# hmi.net
KiCad netlist of a schematic drawn in Altium Designer
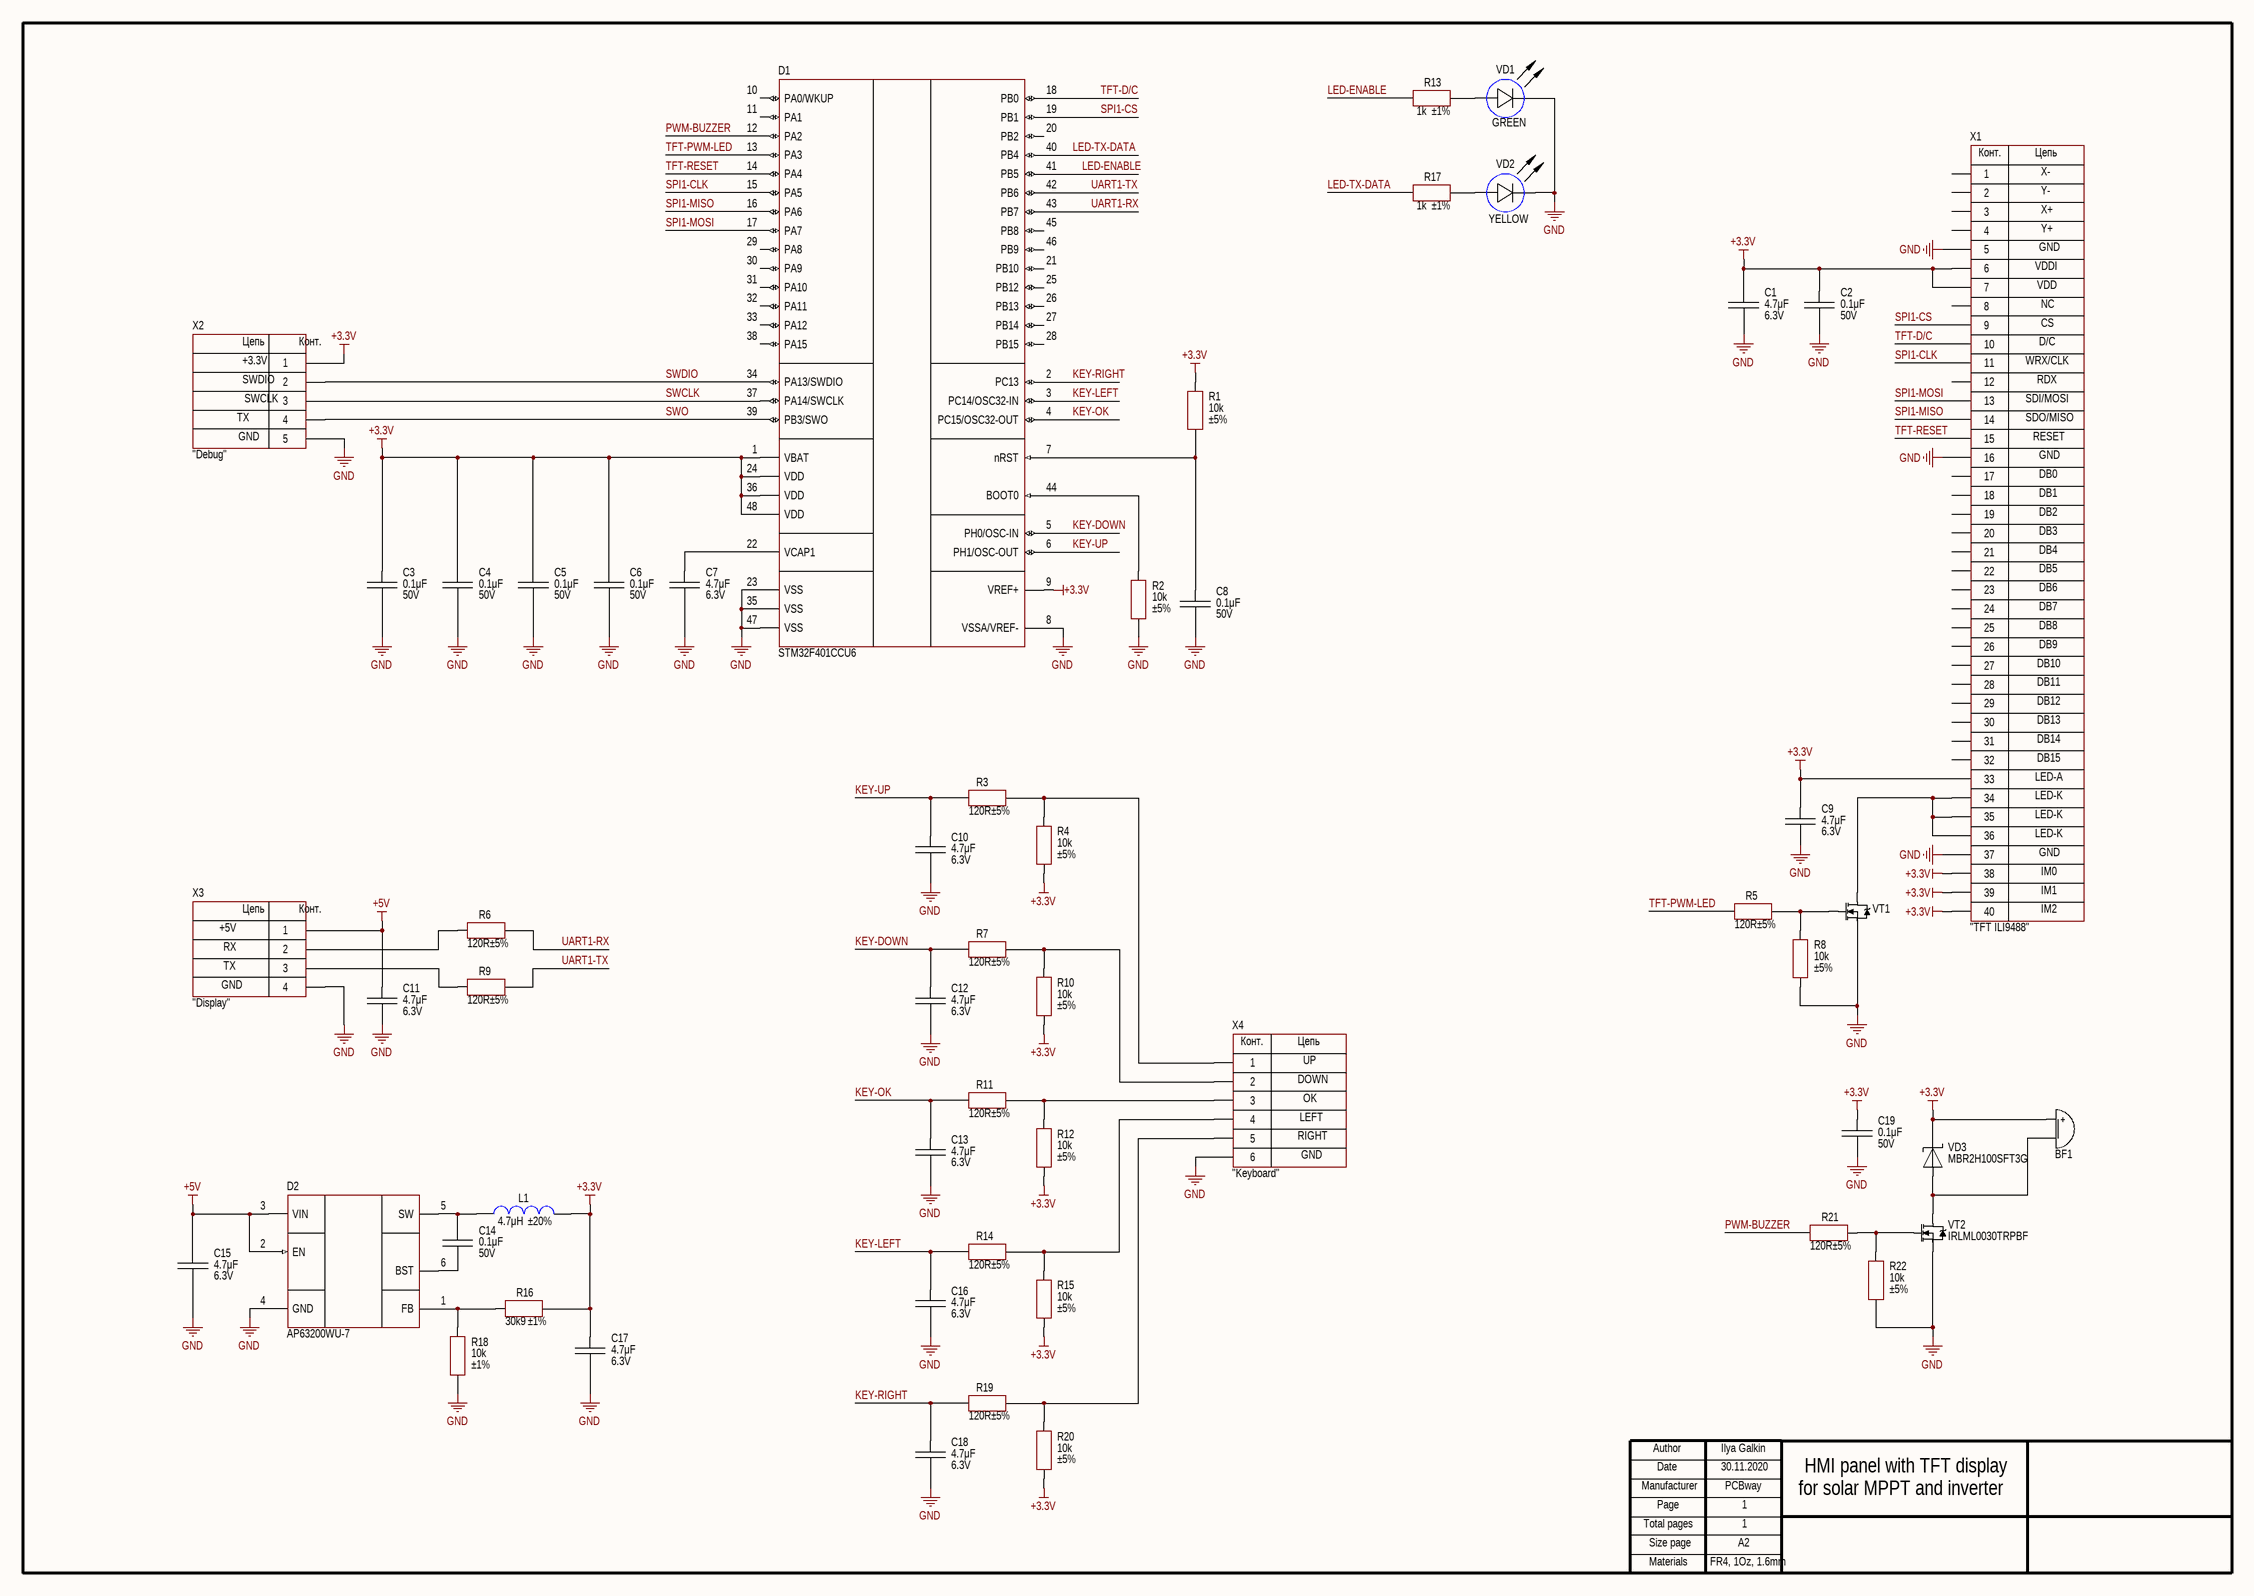
[diagram p0: hmi.SchDoc]

(export (version "E")
  (design (tool "Eeschema 10.0.6"))
  (components
    (comp (ref "BF1")
      (value "~")
      (footprint "BUZ: CMT-7525")
      (fields
        (field (name "MANUFACTURER") "Jiangsu")
        (field (name "VALUEMANUFACTURERPARTNUMBER") "SMD, 7.5x7.5x2.5 mm, 2.7 kHz, 3.6VDC, 80dB, -20...+70°C")
        (field (name "PARTNUMBER") "MLT-7525")
      )
      (libsource (lib "electromechanics") (part "Buzzer"))
    )
    (comp (ref "C1")
      (value "4.7μF")
      (footprint "CAP: 0603")
      (fields
        (field (name "MANUFACTURER") "Samsung")
        (field (name "PARTNUMBER") "CL10B475KQ8NQNC")
        (field (name "VALUEMANUFACTURERPARTNUMBER") "Ceramic capacitor, 4.7μF, X7R, ±10%, 6.3V, 0603, -55...+125°C")
        (field (name "VOLTAGE") "6.3V")
      )
      (libsource (lib "Capacitor") (part "Ceramic_0603"))
    )
    (comp (ref "C2")
      (value "0.1μF")
      (footprint "CAP: 0603")
      (fields
        (field (name "MANUFACTURER") "Samsung")
        (field (name "PARTNUMBER") "CL10B104KB8WPND")
        (field (name "VALUEMANUFACTURERPARTNUMBER") "Ceramic capacitor, 0.1μF, X7R, ±10%, 50V, 0603, -55...+125°C")
        (field (name "VOLTAGE") "50V")
      )
      (libsource (lib "Capacitor") (part "Ceramic_0603"))
    )
    (comp (ref "C3")
      (value "0.1μF")
      (footprint "CAP: 0603")
      (fields
        (field (name "MANUFACTURER") "Samsung")
        (field (name "PARTNUMBER") "CL10B104KB8WPND")
        (field (name "VALUEMANUFACTURERPARTNUMBER") "Ceramic capacitor, 0.1μF, X7R, ±10%, 50V, 0603, -55...+125°C")
        (field (name "VOLTAGE") "50V")
      )
      (libsource (lib "Capacitor") (part "Ceramic_0603"))
    )
    (comp (ref "C4")
      (value "0.1μF")
      (footprint "CAP: 0603")
      (fields
        (field (name "MANUFACTURER") "Samsung")
        (field (name "PARTNUMBER") "CL10B104KB8WPND")
        (field (name "VALUEMANUFACTURERPARTNUMBER") "Ceramic capacitor, 0.1μF, X7R, ±10%, 50V, 0603, -55...+125°C")
        (field (name "VOLTAGE") "50V")
      )
      (libsource (lib "Capacitor") (part "Ceramic_0603"))
    )
    (comp (ref "C5")
      (value "0.1μF")
      (footprint "CAP: 0603")
      (fields
        (field (name "MANUFACTURER") "Samsung")
        (field (name "PARTNUMBER") "CL10B104KB8WPND")
        (field (name "VALUEMANUFACTURERPARTNUMBER") "Ceramic capacitor, 0.1μF, X7R, ±10%, 50V, 0603, -55...+125°C")
        (field (name "VOLTAGE") "50V")
      )
      (libsource (lib "Capacitor") (part "Ceramic_0603"))
    )
    (comp (ref "C6")
      (value "0.1μF")
      (footprint "CAP: 0603")
      (fields
        (field (name "MANUFACTURER") "Samsung")
        (field (name "PARTNUMBER") "CL10B104KB8WPND")
        (field (name "VALUEMANUFACTURERPARTNUMBER") "Ceramic capacitor, 0.1μF, X7R, ±10%, 50V, 0603, -55...+125°C")
        (field (name "VOLTAGE") "50V")
      )
      (libsource (lib "Capacitor") (part "Ceramic_0603"))
    )
    (comp (ref "C7")
      (value "4.7μF")
      (footprint "CAP: 0603")
      (fields
        (field (name "MANUFACTURER") "Samsung")
        (field (name "PARTNUMBER") "CL10B475KQ8NQNC")
        (field (name "VALUEMANUFACTURERPARTNUMBER") "Ceramic capacitor, 4.7μF, X7R, ±10%, 6.3V, 0603, -55...+125°C")
        (field (name "VOLTAGE") "6.3V")
      )
      (libsource (lib "Capacitor") (part "Ceramic_0603"))
    )
    (comp (ref "C8")
      (value "0.1μF")
      (footprint "CAP: 0603")
      (fields
        (field (name "MANUFACTURER") "Samsung")
        (field (name "PARTNUMBER") "CL10B104KB8WPND")
        (field (name "VALUEMANUFACTURERPARTNUMBER") "Ceramic capacitor, 0.1μF, X7R, ±10%, 50V, 0603, -55...+125°C")
        (field (name "VOLTAGE") "50V")
      )
      (libsource (lib "Capacitor") (part "Ceramic_0603"))
    )
    (comp (ref "C9")
      (value "4.7μF")
      (footprint "CAP: 0603")
      (fields
        (field (name "MANUFACTURER") "Samsung")
        (field (name "PARTNUMBER") "CL10B475KQ8NQNC")
        (field (name "VALUEMANUFACTURERPARTNUMBER") "Ceramic capacitor, 4.7μF, X7R, ±10%, 6.3V, 0603, -55...+125°C")
        (field (name "VOLTAGE") "6.3V")
      )
      (libsource (lib "Capacitor") (part "Ceramic_0603"))
    )
    (comp (ref "C10")
      (value "4.7μF")
      (footprint "CAP: 0603")
      (fields
        (field (name "MANUFACTURER") "Samsung")
        (field (name "PARTNUMBER") "CL10B475KQ8NQNC")
        (field (name "VALUEMANUFACTURERPARTNUMBER") "Ceramic capacitor, 4.7μF, X7R, ±10%, 6.3V, 0603, -55...+125°C")
        (field (name "VOLTAGE") "6.3V")
      )
      (libsource (lib "Capacitor") (part "Ceramic_0603"))
    )
    (comp (ref "C11")
      (value "4.7μF")
      (footprint "CAP: 0603")
      (fields
        (field (name "MANUFACTURER") "Samsung")
        (field (name "PARTNUMBER") "CL10B475KQ8NQNC")
        (field (name "VALUEMANUFACTURERPARTNUMBER") "Ceramic capacitor, 4.7μF, X7R, ±10%, 6.3V, 0603, -55...+125°C")
        (field (name "VOLTAGE") "6.3V")
      )
      (libsource (lib "Capacitor") (part "Ceramic_0603"))
    )
    (comp (ref "C12")
      (value "4.7μF")
      (footprint "CAP: 0603")
      (fields
        (field (name "MANUFACTURER") "Samsung")
        (field (name "PARTNUMBER") "CL10B475KQ8NQNC")
        (field (name "VALUEMANUFACTURERPARTNUMBER") "Ceramic capacitor, 4.7μF, X7R, ±10%, 6.3V, 0603, -55...+125°C")
        (field (name "VOLTAGE") "6.3V")
      )
      (libsource (lib "Capacitor") (part "Ceramic_0603"))
    )
    (comp (ref "C13")
      (value "4.7μF")
      (footprint "CAP: 0603")
      (fields
        (field (name "MANUFACTURER") "Samsung")
        (field (name "PARTNUMBER") "CL10B475KQ8NQNC")
        (field (name "VALUEMANUFACTURERPARTNUMBER") "Ceramic capacitor, 4.7μF, X7R, ±10%, 6.3V, 0603, -55...+125°C")
        (field (name "VOLTAGE") "6.3V")
      )
      (libsource (lib "Capacitor") (part "Ceramic_0603"))
    )
    (comp (ref "C14")
      (value "0.1μF")
      (footprint "CAP: 0603")
      (fields
        (field (name "MANUFACTURER") "Samsung")
        (field (name "PARTNUMBER") "CL10B104KB8WPND")
        (field (name "VALUEMANUFACTURERPARTNUMBER") "Ceramic capacitor, 0.1μF, X7R, ±10%, 50V, 0603, -55...+125°C")
        (field (name "VOLTAGE") "50V")
      )
      (libsource (lib "Capacitor") (part "Ceramic_0603"))
    )
    (comp (ref "C15")
      (value "4.7μF")
      (footprint "CAP: 0603")
      (fields
        (field (name "MANUFACTURER") "Samsung")
        (field (name "PARTNUMBER") "CL10B475KQ8NQNC")
        (field (name "VALUEMANUFACTURERPARTNUMBER") "Ceramic capacitor, 4.7μF, X7R, ±10%, 6.3V, 0603, -55...+125°C")
        (field (name "VOLTAGE") "6.3V")
      )
      (libsource (lib "Capacitor") (part "Ceramic_0603"))
    )
    (comp (ref "C16")
      (value "4.7μF")
      (footprint "CAP: 0603")
      (fields
        (field (name "MANUFACTURER") "Samsung")
        (field (name "PARTNUMBER") "CL10B475KQ8NQNC")
        (field (name "VALUEMANUFACTURERPARTNUMBER") "Ceramic capacitor, 4.7μF, X7R, ±10%, 6.3V, 0603, -55...+125°C")
        (field (name "VOLTAGE") "6.3V")
      )
      (libsource (lib "Capacitor") (part "Ceramic_0603"))
    )
    (comp (ref "C17")
      (value "4.7μF")
      (footprint "CAP: 0603")
      (fields
        (field (name "MANUFACTURER") "Samsung")
        (field (name "PARTNUMBER") "CL10B475KQ8NQNC")
        (field (name "VALUEMANUFACTURERPARTNUMBER") "Ceramic capacitor, 4.7μF, X7R, ±10%, 6.3V, 0603, -55...+125°C")
        (field (name "VOLTAGE") "6.3V")
      )
      (libsource (lib "Capacitor") (part "Ceramic_0603"))
    )
    (comp (ref "C18")
      (value "4.7μF")
      (footprint "CAP: 0603")
      (fields
        (field (name "MANUFACTURER") "Samsung")
        (field (name "PARTNUMBER") "CL10B475KQ8NQNC")
        (field (name "VALUEMANUFACTURERPARTNUMBER") "Ceramic capacitor, 4.7μF, X7R, ±10%, 6.3V, 0603, -55...+125°C")
        (field (name "VOLTAGE") "6.3V")
      )
      (libsource (lib "Capacitor") (part "Ceramic_0603"))
    )
    (comp (ref "C19")
      (value "0.1μF")
      (footprint "CAP: 0603")
      (fields
        (field (name "MANUFACTURER") "Samsung")
        (field (name "PARTNUMBER") "CL10B104KB8WPND")
        (field (name "VALUEMANUFACTURERPARTNUMBER") "Ceramic capacitor, 0.1μF, X7R, ±10%, 50V, 0603, -55...+125°C")
        (field (name "VOLTAGE") "50V")
      )
      (libsource (lib "Capacitor") (part "Ceramic_0603"))
    )
    (comp (ref "D1")
      (value "~")
      (footprint "48-QFN (7x7)")
      (description "Cortex-M4")
      (fields (field (name "MANUFACTURER") "STMicroelectronics") (field (name "PARTNUMBER") "STM32F401CCU6"))
      (libsource (lib "ic-mcu") (part "STM32F401CCU6"))
    )
    (comp (ref "D2")
      (value "~")
      (footprint "SOT23-6")
      (description "Buck converter")
      (fields
        (field (name "MANUFACTURER") "Diodes")
        (field (name "VALUEMANUFACTURERPARTNUMBER") "DC/DC buck converter, input 3.8...32V, 500kHz, output 1.2...12V, 2A, -40...+85°C, SOT23-6")
        (field (name "PARTNUMBER") "AP63200WU-7")
      )
      (libsource (lib "ic-power-supply") (part "AP63200WU-7"))
    )
    (comp (ref "L1")
      (value "4.7μH")
      (footprint "IND: CD32")
      (fields
        (field (name "MANUFACTURER") "YJYCOIN")
        (field (name "PARTNUMBER") "CD32YP0302-4R7M")
        (field (name "VALUEMANUFACTURERPARTNUMBER") "Fixed inductor, 4.7μH, ±20%, CD32 series, 1.5A, -40...+125°C")
        (field (name "TOLERANCE") "±20%")
      )
      (libsource (lib "inductor") (part "Inductor_CD32"))
    )
    (comp (ref "R1")
      (value "10k")
      (footprint "RES: 0603")
      (fields
        (field (name "MANUFACTURER") "Yageo")
        (field (name "PARTNUMBER") "RC0603JR-0710KL")
        (field (name "VALUEMANUFACTURERPARTNUMBER") "Resistor film, 10k, ±5%, 0603, 0.1W, -55...+125°C")
        (field (name "TOLERANCE") "±5%")
      )
      (libsource (lib "Resistor") (part "Resistor_0603"))
    )
    (comp (ref "R2")
      (value "10k")
      (footprint "RES: 0603")
      (fields
        (field (name "MANUFACTURER") "Yageo")
        (field (name "PARTNUMBER") "RC0603JR-0710KL")
        (field (name "VALUEMANUFACTURERPARTNUMBER") "Resistor film, 10k, ±5%, 0603, 0.1W, -55...+125°C")
        (field (name "TOLERANCE") "±5%")
      )
      (libsource (lib "Resistor") (part "Resistor_0603"))
    )
    (comp (ref "R3")
      (value "120R")
      (footprint "RES: 0603")
      (fields
        (field (name "MANUFACTURER") "Yageo")
        (field (name "PARTNUMBER") "RC0603JR-07120RL")
        (field (name "VALUEMANUFACTURERPARTNUMBER") "Resistor film, 120R, ±5%, 0603, 0.1W, -55...+125°C")
        (field (name "TOLERANCE") "±5%")
      )
      (libsource (lib "resistor") (part "Resistor_0603"))
    )
    (comp (ref "R4")
      (value "10k")
      (footprint "RES: 0603")
      (fields
        (field (name "MANUFACTURER") "Yageo")
        (field (name "PARTNUMBER") "RC0603JR-0710KL")
        (field (name "VALUEMANUFACTURERPARTNUMBER") "Resistor film, 10k, ±5%, 0603, 0.1W, -55...+125°C")
        (field (name "TOLERANCE") "±5%")
      )
      (libsource (lib "Resistor") (part "Resistor_0603"))
    )
    (comp (ref "R5")
      (value "120R")
      (footprint "RES: 0603")
      (fields
        (field (name "MANUFACTURER") "Yageo")
        (field (name "PARTNUMBER") "RC0603JR-07120RL")
        (field (name "VALUEMANUFACTURERPARTNUMBER") "Resistor film, 120R, ±5%, 0603, 0.1W, -55...+125°C")
        (field (name "TOLERANCE") "±5%")
      )
      (libsource (lib "") (part "Resistor_0603_1"))
    )
    (comp (ref "R6")
      (value "120R")
      (footprint "RES: 0603")
      (fields
        (field (name "MANUFACTURER") "Yageo")
        (field (name "PARTNUMBER") "RC0603JR-07120RL")
        (field (name "VALUEMANUFACTURERPARTNUMBER") "Resistor film, 120R, ±5%, 0603, 0.1W, -55...+125°C")
        (field (name "TOLERANCE") "±5%")
      )
      (libsource (lib "") (part "Resistor_0603_1"))
    )
    (comp (ref "R7")
      (value "120R")
      (footprint "RES: 0603")
      (fields
        (field (name "MANUFACTURER") "Yageo")
        (field (name "PARTNUMBER") "RC0603JR-07120RL")
        (field (name "VALUEMANUFACTURERPARTNUMBER") "Resistor film, 120R, ±5%, 0603, 0.1W, -55...+125°C")
        (field (name "TOLERANCE") "±5%")
      )
      (libsource (lib "resistor") (part "Resistor_0603"))
    )
    (comp (ref "R8")
      (value "10k")
      (footprint "RES: 0603")
      (fields
        (field (name "MANUFACTURER") "Yageo")
        (field (name "PARTNUMBER") "RC0603JR-0710KL")
        (field (name "VALUEMANUFACTURERPARTNUMBER") "Resistor film, 10k, ±5%, 0603, 0.1W, -55...+125°C")
        (field (name "TOLERANCE") "±5%")
      )
      (libsource (lib "Resistor") (part "Resistor_0603"))
    )
    (comp (ref "R9")
      (value "120R")
      (footprint "RES: 0603")
      (fields
        (field (name "MANUFACTURER") "Yageo")
        (field (name "PARTNUMBER") "RC0603JR-07120RL")
        (field (name "VALUEMANUFACTURERPARTNUMBER") "Resistor film, 120R, ±5%, 0603, 0.1W, -55...+125°C")
        (field (name "TOLERANCE") "±5%")
      )
      (libsource (lib "") (part "Resistor_0603_1"))
    )
    (comp (ref "R10")
      (value "10k")
      (footprint "RES: 0603")
      (fields
        (field (name "MANUFACTURER") "Yageo")
        (field (name "PARTNUMBER") "RC0603JR-0710KL")
        (field (name "VALUEMANUFACTURERPARTNUMBER") "Resistor film, 10k, ±5%, 0603, 0.1W, -55...+125°C")
        (field (name "TOLERANCE") "±5%")
      )
      (libsource (lib "Resistor") (part "Resistor_0603"))
    )
    (comp (ref "R11")
      (value "120R")
      (footprint "RES: 0603")
      (fields
        (field (name "MANUFACTURER") "Yageo")
        (field (name "PARTNUMBER") "RC0603JR-07120RL")
        (field (name "VALUEMANUFACTURERPARTNUMBER") "Resistor film, 120R, ±5%, 0603, 0.1W, -55...+125°C")
        (field (name "TOLERANCE") "±5%")
      )
      (libsource (lib "resistor") (part "Resistor_0603"))
    )
    (comp (ref "R12")
      (value "10k")
      (footprint "RES: 0603")
      (fields
        (field (name "MANUFACTURER") "Yageo")
        (field (name "PARTNUMBER") "RC0603JR-0710KL")
        (field (name "VALUEMANUFACTURERPARTNUMBER") "Resistor film, 10k, ±5%, 0603, 0.1W, -55...+125°C")
        (field (name "TOLERANCE") "±5%")
      )
      (libsource (lib "Resistor") (part "Resistor_0603"))
    )
    (comp (ref "R13")
      (value "1k")
      (footprint "RES: 0603")
      (fields
        (field (name "MANUFACTURER") "Yageo")
        (field (name "PARTNUMBER") "RC0603JR-071KL")
        (field (name "VALUEMANUFACTURERPARTNUMBER") "Resistor film, 1k, ±1%, 0603, 0.1W, -55...+125°C")
        (field (name "TOLERANCE") "±1%")
      )
      (libsource (lib "") (part "Resistor_0603_2"))
    )
    (comp (ref "R14")
      (value "120R")
      (footprint "RES: 0603")
      (fields
        (field (name "MANUFACTURER") "Yageo")
        (field (name "PARTNUMBER") "RC0603JR-07120RL")
        (field (name "VALUEMANUFACTURERPARTNUMBER") "Resistor film, 120R, ±5%, 0603, 0.1W, -55...+125°C")
        (field (name "TOLERANCE") "±5%")
      )
      (libsource (lib "resistor") (part "Resistor_0603"))
    )
    (comp (ref "R15")
      (value "10k")
      (footprint "RES: 0603")
      (fields
        (field (name "MANUFACTURER") "Yageo")
        (field (name "PARTNUMBER") "RC0603JR-0710KL")
        (field (name "VALUEMANUFACTURERPARTNUMBER") "Resistor film, 10k, ±5%, 0603, 0.1W, -55...+125°C")
        (field (name "TOLERANCE") "±5%")
      )
      (libsource (lib "Resistor") (part "Resistor_0603"))
    )
    (comp (ref "R16")
      (value "30k9")
      (footprint "RES: 0603")
      (fields
        (field (name "MANUFACTURER") "Yageo")
        (field (name "PARTNUMBER") "RC0603FR-0730K9L")
        (field (name "VALUEMANUFACTURERPARTNUMBER") "Resistor film, 30k9, ±1%, 0603, 0.1W, -55...+125°C")
        (field (name "TOLERANCE") "±1%")
      )
      (libsource (lib "") (part "Resistor_0603_2"))
    )
    (comp (ref "R17")
      (value "1k")
      (footprint "RES: 0603")
      (fields
        (field (name "MANUFACTURER") "Yageo")
        (field (name "PARTNUMBER") "RC0603JR-071KL")
        (field (name "VALUEMANUFACTURERPARTNUMBER") "Resistor film, 1k, ±1%, 0603, 0.1W, -55...+125°C")
        (field (name "TOLERANCE") "±1%")
      )
      (libsource (lib "") (part "Resistor_0603_2"))
    )
    (comp (ref "R18")
      (value "10k")
      (footprint "RES: 0603")
      (fields
        (field (name "MANUFACTURER") "Yageo")
        (field (name "PARTNUMBER") "AC0603FR-0710KL")
        (field (name "VALUEMANUFACTURERPARTNUMBER") "Resistor film, 10k, ±1%, 0603, 0.1W, -55...+125°C")
        (field (name "TOLERANCE") "±1%")
      )
      (libsource (lib "Resistor") (part "Resistor_0603"))
    )
    (comp (ref "R19")
      (value "120R")
      (footprint "RES: 0603")
      (fields
        (field (name "MANUFACTURER") "Yageo")
        (field (name "PARTNUMBER") "RC0603JR-07120RL")
        (field (name "VALUEMANUFACTURERPARTNUMBER") "Resistor film, 120R, ±5%, 0603, 0.1W, -55...+125°C")
        (field (name "TOLERANCE") "±5%")
      )
      (libsource (lib "resistor") (part "Resistor_0603"))
    )
    (comp (ref "R20")
      (value "10k")
      (footprint "RES: 0603")
      (fields
        (field (name "MANUFACTURER") "Yageo")
        (field (name "PARTNUMBER") "RC0603JR-0710KL")
        (field (name "VALUEMANUFACTURERPARTNUMBER") "Resistor film, 10k, ±5%, 0603, 0.1W, -55...+125°C")
        (field (name "TOLERANCE") "±5%")
      )
      (libsource (lib "Resistor") (part "Resistor_0603"))
    )
    (comp (ref "R21")
      (value "120R")
      (footprint "RES: 0603")
      (fields
        (field (name "MANUFACTURER") "Yageo")
        (field (name "PARTNUMBER") "RC0603JR-07120RL")
        (field (name "VALUEMANUFACTURERPARTNUMBER") "Resistor film, 120R, ±5%, 0603, 0.1W, -55...+125°C")
        (field (name "TOLERANCE") "±5%")
      )
      (libsource (lib "") (part "Resistor_0603_1"))
    )
    (comp (ref "R22")
      (value "10k")
      (footprint "RES: 0603")
      (fields
        (field (name "MANUFACTURER") "Yageo")
        (field (name "PARTNUMBER") "RC0603JR-0710KL")
        (field (name "VALUEMANUFACTURERPARTNUMBER") "Resistor film, 10k, ±5%, 0603, 0.1W, -55...+125°C")
        (field (name "TOLERANCE") "±5%")
      )
      (libsource (lib "Resistor") (part "Resistor_0603"))
    )
    (comp (ref "VD1")
      (value "~")
      (footprint "LED: 0603G")
      (fields
        (field (name "MANUFACTURER") "Wurth")
        (field (name "VALUEMANUFACTURERPARTNUMBER") "LED, 20mA, 2V, 0603, -55...+150°C")
        (field (name "PARTNUMBER") "150060VS75000")
        (field (name "COLOR") "GREEN")
      )
      (libsource (lib "Diode") (part "LED_single"))
    )
    (comp (ref "VD2")
      (value "~")
      (footprint "LED: 0603Y")
      (fields
        (field (name "MANUFACTURER") "Wurth")
        (field (name "VALUEMANUFACTURERPARTNUMBER") "LED, 20mA, 2V, 0603, -55...+150°C")
        (field (name "PARTNUMBER") "150060YS75000")
        (field (name "COLOR") "YELLOW")
      )
      (libsource (lib "Diode") (part "LED_single"))
    )
    (comp (ref "VD3")
      (value "~")
      (footprint "DIODE: SOD123F")
      (fields
        (field (name "MANUFACTURER") "ON Semiconductor")
        (field (name "VALUEMANUFACTURERPARTNUMBER") "Schottky diode, 100V, 2A, 840mV, 15pF, SOD-123F, -55...+150°C")
        (field (name "VOLTAGE") "100V")
        (field (name "PARTNUMBER") "MBR2H100SFT3G")
      )
      (libsource (lib "Diode") (part "Schottky_single"))
    )
    (comp (ref "VT1")
      (value "~")
      (footprint "SOT23")
      (fields
        (field (name "MANUFACTURER") "Infineon Technologies")
        (field (name "VALUEMANUFACTURERPARTNUMBER") "MOSFET N-channel transistor, 30V, 5.3A, 2.6nC, 1.3W, 27mOhm, 382pF, SOT-23, -55...+150°C")
        (field (name "PARTNUMBER") "IRLML0030TRPBF")
      )
      (libsource (lib "transistor") (part "MOSFET_N_132"))
    )
    (comp (ref "VT2")
      (value "~")
      (footprint "SOT23")
      (fields
        (field (name "MANUFACTURER") "Infineon Technologies")
        (field (name "VALUEMANUFACTURERPARTNUMBER") "MOSFET N-channel transistor, 30V, 5.3A, 2.6nC, 1.3W, 27mOhm, 382pF, SOT-23, -55...+150°C")
        (field (name "PARTNUMBER") "IRLML0030TRPBF")
      )
      (libsource (lib "transistor") (part "MOSFET_N_132"))
    )
    (comp (ref "X1")
      (value "~")
      (footprint "CON: FFC/FPC-40-0.5")
      (fields
        (field (name "MANUFACTURER") "JUSHUO")
        (field (name "VALUEMANUFACTURERPARTNUMBER") "Connector, 40pin, 0.5mm, FFC/FPC, Top contact")
        (field (name "PARTNUMBER") "AFC07-S40ECC-00")
        (field (name "COMMENTTEXT") "\"TFT ILI9488\"")
      )
      (libsource (lib "connector") (part "Connector_FFC_40"))
    )
    (comp (ref "X2")
      (value "~")
      (footprint "CON: PLS-5")
      (fields
        (field (name "MANUFACTURER") "Connfly")
        (field (name "VALUEMANUFACTURERPARTNUMBER") "Connector, 5pin, 2.54mm, 500VAC, 3A")
        (field (name "PARTNUMBER") "PLS-5")
        (field (name "COMMENTTEXT") "\"Debug\"")
      )
      (libsource (lib "connector") (part "PLS-5"))
    )
    (comp (ref "X3")
      (value "~")
      (footprint "CON: CWF-4R")
      (fields
        (field (name "MANUFACTURER") "Connfly")
        (field (name "VALUEMANUFACTURERPARTNUMBER") "Connector, 4pin, 2.54mm, 250VAC, 3A")
        (field (name "PARTNUMBER") "CWF-4R")
        (field (name "COMMENTTEXT") "\"Display\"")
      )
      (libsource (lib "connector") (part "CWF-4"))
    )
    (comp (ref "X4")
      (value "~")
      (footprint "CON: CWF-6R")
      (fields
        (field (name "MANUFACTURER") "Connfly")
        (field (name "VALUEMANUFACTURERPARTNUMBER") "Connector, 6pin, 2.54mm, 250VAC, 3A")
        (field (name "PARTNUMBER") "CWF-6R")
        (field (name "COMMENTTEXT") "\"Keyboard\"")
      )
      (libsource (lib "connector") (part "CWF-6"))
    )
  )
  (nets
    (net (code "1") (name "+3.3V") (class "Default")
      (node (ref "BF1") (pin "1") (pinfunction "+_1") (pintype "passive"))
      (node (ref "C1") (pin "2") (pinfunction "2_2") (pintype "power_in"))
      (node (ref "C17") (pin "2") (pinfunction "2_2") (pintype "power_in"))
      (node (ref "C19") (pin "2") (pinfunction "2_2") (pintype "power_in"))
      (node (ref "C2") (pin "2") (pinfunction "2_2") (pintype "power_in"))
      (node (ref "C3") (pin "2") (pinfunction "2_2") (pintype "power_in"))
      (node (ref "C4") (pin "2") (pinfunction "2_2") (pintype "power_in"))
      (node (ref "C5") (pin "2") (pinfunction "2_2") (pintype "power_in"))
      (node (ref "C6") (pin "2") (pinfunction "2_2") (pintype "power_in"))
      (node (ref "C9") (pin "2") (pinfunction "2_2") (pintype "power_in"))
      (node (ref "D1") (pin "1") (pinfunction "VBAT_1") (pintype "passive"))
      (node (ref "D1") (pin "24") (pinfunction "VDD_24") (pintype "passive"))
      (node (ref "D1") (pin "36") (pinfunction "VDD_36") (pintype "passive"))
      (node (ref "D1") (pin "48") (pinfunction "VDD_48") (pintype "passive"))
      (node (ref "D1") (pin "9") (pinfunction "VREF+_9") (pintype "passive"))
      (node (ref "L1") (pin "1") (pinfunction "1_1") (pintype "passive"))
      (node (ref "R1") (pin "2") (pinfunction "2_2") (pintype "passive"))
      (node (ref "R10") (pin "1") (pinfunction "1_1") (pintype "passive"))
      (node (ref "R12") (pin "1") (pinfunction "1_1") (pintype "passive"))
      (node (ref "R15") (pin "1") (pinfunction "1_1") (pintype "passive"))
      (node (ref "R16") (pin "1") (pinfunction "1_1") (pintype "passive"))
      (node (ref "R20") (pin "1") (pinfunction "1_1") (pintype "passive"))
      (node (ref "R4") (pin "1") (pinfunction "1_1") (pintype "passive"))
      (node (ref "VD3") (pin "2") (pinfunction "2_2") (pintype "passive"))
      (node (ref "X1") (pin "33") (pinfunction "33_33") (pintype "passive"))
      (node (ref "X1") (pin "38") (pinfunction "38_38") (pintype "passive"))
      (node (ref "X1") (pin "39") (pinfunction "39_39") (pintype "passive"))
      (node (ref "X1") (pin "40") (pinfunction "40_40") (pintype "passive"))
      (node (ref "X1") (pin "6") (pinfunction "6_6") (pintype "passive"))
      (node (ref "X1") (pin "7") (pinfunction "7_7") (pintype "passive"))
      (node (ref "X2") (pin "1") (pinfunction "1_1") (pintype "passive"))
    )
    (net (code "2") (name "+5V") (class "Default")
      (node (ref "C11") (pin "2") (pinfunction "2_2") (pintype "power_in"))
      (node (ref "C15") (pin "2") (pinfunction "2_2") (pintype "power_in"))
      (node (ref "D2") (pin "2") (pinfunction "EN_2") (pintype "input"))
      (node (ref "D2") (pin "3") (pinfunction "VIN_3") (pintype "passive"))
      (node (ref "X3") (pin "1") (pinfunction "1_1") (pintype "passive"))
    )
    (net (code "3") (name "/KEY-DOWN") (class "Default")
      (node (ref "C12") (pin "2") (pinfunction "2_2") (pintype "power_in"))
      (node (ref "D1") (pin "5") (pinfunction "PH0/OSC-IN_5") (pintype "bidirectional"))
      (node (ref "R7") (pin "1") (pinfunction "1_1") (pintype "passive"))
    )
    (net (code "4") (name "/KEY-LEFT") (class "Default")
      (node (ref "C16") (pin "2") (pinfunction "2_2") (pintype "power_in"))
      (node (ref "D1") (pin "3") (pinfunction "PC14/OSC32-IN_3") (pintype "bidirectional"))
      (node (ref "R14") (pin "1") (pinfunction "1_1") (pintype "passive"))
    )
    (net (code "5") (name "/KEY-OK") (class "Default")
      (node (ref "C13") (pin "2") (pinfunction "2_2") (pintype "power_in"))
      (node (ref "D1") (pin "4") (pinfunction "PC15/OSC32-OUT_4") (pintype "bidirectional"))
      (node (ref "R11") (pin "1") (pinfunction "1_1") (pintype "passive"))
    )
    (net (code "6") (name "/KEY-RIGHT") (class "Default")
      (node (ref "C18") (pin "2") (pinfunction "2_2") (pintype "power_in"))
      (node (ref "D1") (pin "2") (pinfunction "PC13_2") (pintype "bidirectional"))
      (node (ref "R19") (pin "1") (pinfunction "1_1") (pintype "passive"))
    )
    (net (code "7") (name "/KEY-UP") (class "Default")
      (node (ref "C10") (pin "2") (pinfunction "2_2") (pintype "power_in"))
      (node (ref "D1") (pin "6") (pinfunction "PH1/OSC-OUT_6") (pintype "bidirectional"))
      (node (ref "R3") (pin "1") (pinfunction "1_1") (pintype "passive"))
    )
    (net (code "8") (name "/LED-ENABLE") (class "Default")
      (node (ref "D1") (pin "41") (pinfunction "PB5_41") (pintype "bidirectional"))
      (node (ref "R13") (pin "2") (pinfunction "2_2") (pintype "passive"))
    )
    (net (code "9") (name "/LED-TX-DATA") (class "Default")
      (node (ref "D1") (pin "40") (pinfunction "PB4_40") (pintype "bidirectional"))
      (node (ref "R17") (pin "2") (pinfunction "2_2") (pintype "passive"))
    )
    (net (code "10") (name "/PWM-BUZZER") (class "Default")
      (node (ref "D1") (pin "12") (pinfunction "PA2_12") (pintype "bidirectional"))
      (node (ref "R21") (pin "1") (pinfunction "1_1") (pintype "passive"))
    )
    (net (code "11") (name "/SPI1-CLK") (class "Default")
      (node (ref "D1") (pin "15") (pinfunction "PA5_15") (pintype "bidirectional"))
      (node (ref "X1") (pin "11") (pinfunction "11_11") (pintype "passive"))
    )
    (net (code "12") (name "/SPI1-CS") (class "Default")
      (node (ref "D1") (pin "19") (pinfunction "PB1_19") (pintype "bidirectional"))
      (node (ref "X1") (pin "9") (pinfunction "9_9") (pintype "passive"))
    )
    (net (code "13") (name "/SPI1-MISO") (class "Default")
      (node (ref "D1") (pin "16") (pinfunction "PA6_16") (pintype "bidirectional"))
      (node (ref "X1") (pin "14") (pinfunction "14_14") (pintype "passive"))
    )
    (net (code "14") (name "/SPI1-MOSI") (class "Default")
      (node (ref "D1") (pin "17") (pinfunction "PA7_17") (pintype "bidirectional"))
      (node (ref "X1") (pin "13") (pinfunction "13_13") (pintype "passive"))
    )
    (net (code "15") (name "/SWCLK") (class "Default")
      (node (ref "D1") (pin "37") (pinfunction "PA14/SWCLK_37") (pintype "bidirectional"))
      (node (ref "X2") (pin "3") (pinfunction "3_3") (pintype "power_in"))
    )
    (net (code "16") (name "/SWDIO") (class "Default")
      (node (ref "D1") (pin "34") (pinfunction "PA13/SWDIO_34") (pintype "bidirectional"))
      (node (ref "X2") (pin "2") (pinfunction "2_2") (pintype "passive"))
    )
    (net (code "17") (name "/SWO") (class "Default")
      (node (ref "D1") (pin "39") (pinfunction "PB3/SWO_39") (pintype "bidirectional"))
      (node (ref "X2") (pin "4") (pinfunction "4_4") (pintype "power_in"))
    )
    (net (code "18") (name "/TFT-D{slash}C") (class "Default")
      (node (ref "D1") (pin "18") (pinfunction "PB0_18") (pintype "bidirectional"))
      (node (ref "X1") (pin "10") (pinfunction "10_10") (pintype "passive"))
    )
    (net (code "19") (name "/TFT-PWM-LED") (class "Default")
      (node (ref "D1") (pin "13") (pinfunction "PA3_13") (pintype "bidirectional"))
      (node (ref "R5") (pin "1") (pinfunction "1_1") (pintype "passive"))
    )
    (net (code "20") (name "/TFT-RESET") (class "Default")
      (node (ref "D1") (pin "14") (pinfunction "PA4_14") (pintype "bidirectional"))
      (node (ref "X1") (pin "15") (pinfunction "15_15") (pintype "passive"))
    )
    (net (code "21") (name "/UART1-RX") (class "Default")
      (node (ref "D1") (pin "43") (pinfunction "PB7_43") (pintype "bidirectional"))
      (node (ref "R6") (pin "2") (pinfunction "2_2") (pintype "passive"))
    )
    (net (code "22") (name "/UART1-TX") (class "Default")
      (node (ref "D1") (pin "42") (pinfunction "PB6_42") (pintype "bidirectional"))
      (node (ref "R9") (pin "2") (pinfunction "2_2") (pintype "passive"))
    )
    (net (code "23") (name "GND") (class "Default")
      (node (ref "C1") (pin "1") (pinfunction "1_1") (pintype "power_in"))
      (node (ref "C10") (pin "1") (pinfunction "1_1") (pintype "power_in"))
      (node (ref "C11") (pin "1") (pinfunction "1_1") (pintype "power_in"))
      (node (ref "C12") (pin "1") (pinfunction "1_1") (pintype "power_in"))
      (node (ref "C13") (pin "1") (pinfunction "1_1") (pintype "power_in"))
      (node (ref "C15") (pin "1") (pinfunction "1_1") (pintype "power_in"))
      (node (ref "C16") (pin "1") (pinfunction "1_1") (pintype "power_in"))
      (node (ref "C17") (pin "1") (pinfunction "1_1") (pintype "power_in"))
      (node (ref "C18") (pin "1") (pinfunction "1_1") (pintype "power_in"))
      (node (ref "C19") (pin "1") (pinfunction "1_1") (pintype "power_in"))
      (node (ref "C2") (pin "1") (pinfunction "1_1") (pintype "power_in"))
      (node (ref "C3") (pin "1") (pinfunction "1_1") (pintype "power_in"))
      (node (ref "C4") (pin "1") (pinfunction "1_1") (pintype "power_in"))
      (node (ref "C5") (pin "1") (pinfunction "1_1") (pintype "power_in"))
      (node (ref "C6") (pin "1") (pinfunction "1_1") (pintype "power_in"))
      (node (ref "C7") (pin "1") (pinfunction "1_1") (pintype "power_in"))
      (node (ref "C8") (pin "1") (pinfunction "1_1") (pintype "power_in"))
      (node (ref "C9") (pin "1") (pinfunction "1_1") (pintype "power_in"))
      (node (ref "D1") (pin "23") (pinfunction "VSS_23") (pintype "passive"))
      (node (ref "D1") (pin "35") (pinfunction "VSS_35") (pintype "passive"))
      (node (ref "D1") (pin "47") (pinfunction "VSS_47") (pintype "passive"))
      (node (ref "D1") (pin "8") (pinfunction "VSSA/VREF-_8") (pintype "passive"))
      (node (ref "D2") (pin "4") (pinfunction "GND_4") (pintype "passive"))
      (node (ref "R18") (pin "1") (pinfunction "1_1") (pintype "passive"))
      (node (ref "R2") (pin "1") (pinfunction "1_1") (pintype "passive"))
      (node (ref "R22") (pin "1") (pinfunction "1_1") (pintype "passive"))
      (node (ref "R8") (pin "1") (pinfunction "1_1") (pintype "passive"))
      (node (ref "VD1") (pin "2") (pinfunction "C_2") (pintype "passive"))
      (node (ref "VD2") (pin "2") (pinfunction "C_2") (pintype "passive"))
      (node (ref "VT1") (pin "2") (pinfunction "S_2") (pintype "passive"))
      (node (ref "VT2") (pin "2") (pinfunction "S_2") (pintype "passive"))
      (node (ref "X1") (pin "16") (pinfunction "16_16") (pintype "passive"))
      (node (ref "X1") (pin "37") (pinfunction "37_37") (pintype "passive"))
      (node (ref "X1") (pin "5") (pinfunction "5_5") (pintype "passive"))
      (node (ref "X2") (pin "5") (pinfunction "5_5") (pintype "power_in"))
      (node (ref "X3") (pin "4") (pinfunction "4_4") (pintype "power_in"))
      (node (ref "X4") (pin "6") (pinfunction "6_6") (pintype "power_in"))
    )
    (net (code "24") (name "Net-(BF1--)") (class "Default")
      (node (ref "BF1") (pin "2") (pinfunction "-_2") (pintype "passive"))
      (node (ref "VD3") (pin "1") (pinfunction "1_1") (pintype "passive"))
      (node (ref "VT2") (pin "3") (pinfunction "D_3") (pintype "passive"))
    )
    (net (code "25") (name "Net-(D1-BOOT0)") (class "Default")
      (node (ref "D1") (pin "44") (pinfunction "BOOT0_44") (pintype "input"))
      (node (ref "R2") (pin "2") (pinfunction "2_2") (pintype "passive"))
    )
    (net (code "26") (name "Net-(D1-VCAP1)") (class "Default")
      (node (ref "C7") (pin "2") (pinfunction "2_2") (pintype "power_in"))
      (node (ref "D1") (pin "22") (pinfunction "VCAP1_22") (pintype "passive"))
    )
    (net (code "27") (name "Net-(D1-nRST)") (class "Default")
      (node (ref "C8") (pin "2") (pinfunction "2_2") (pintype "power_in"))
      (node (ref "D1") (pin "7") (pinfunction "nRST_7") (pintype "input"))
      (node (ref "R1") (pin "1") (pinfunction "1_1") (pintype "passive"))
    )
    (net (code "28") (name "Net-(D2-BST)") (class "Default")
      (node (ref "C14") (pin "1") (pinfunction "1_1") (pintype "power_in"))
      (node (ref "D2") (pin "6") (pinfunction "BST_6") (pintype "passive"))
    )
    (net (code "29") (name "Net-(D2-FB)") (class "Default")
      (node (ref "D2") (pin "1") (pinfunction "FB_1") (pintype "passive"))
      (node (ref "R16") (pin "2") (pinfunction "2_2") (pintype "passive"))
      (node (ref "R18") (pin "2") (pinfunction "2_2") (pintype "passive"))
    )
    (net (code "30") (name "Net-(D2-SW)") (class "Default")
      (node (ref "C14") (pin "2") (pinfunction "2_2") (pintype "power_in"))
      (node (ref "D2") (pin "5") (pinfunction "SW_5") (pintype "passive"))
      (node (ref "L1") (pin "2") (pinfunction "2_2") (pintype "passive"))
    )
    (net (code "31") (name "Net-(R3-Pad2)") (class "Default")
      (node (ref "R3") (pin "2") (pinfunction "2_2") (pintype "passive"))
      (node (ref "R4") (pin "2") (pinfunction "2_2") (pintype "passive"))
      (node (ref "X4") (pin "1") (pinfunction "1_1") (pintype "passive"))
    )
    (net (code "32") (name "Net-(R6-Pad1)") (class "Default")
      (node (ref "R6") (pin "1") (pinfunction "1_1") (pintype "passive"))
      (node (ref "X3") (pin "2") (pinfunction "2_2") (pintype "passive"))
    )
    (net (code "33") (name "Net-(R9-Pad1)") (class "Default")
      (node (ref "R9") (pin "1") (pinfunction "1_1") (pintype "passive"))
      (node (ref "X3") (pin "3") (pinfunction "3_3") (pintype "power_in"))
    )
    (net (code "34") (name "Net-(R10-Pad2)") (class "Default")
      (node (ref "R10") (pin "2") (pinfunction "2_2") (pintype "passive"))
      (node (ref "R7") (pin "2") (pinfunction "2_2") (pintype "passive"))
      (node (ref "X4") (pin "2") (pinfunction "2_2") (pintype "passive"))
    )
    (net (code "35") (name "Net-(R11-Pad2)") (class "Default")
      (node (ref "R11") (pin "2") (pinfunction "2_2") (pintype "passive"))
      (node (ref "R12") (pin "2") (pinfunction "2_2") (pintype "passive"))
      (node (ref "X4") (pin "3") (pinfunction "3_3") (pintype "power_in"))
    )
    (net (code "36") (name "Net-(R14-Pad2)") (class "Default")
      (node (ref "R14") (pin "2") (pinfunction "2_2") (pintype "passive"))
      (node (ref "R15") (pin "2") (pinfunction "2_2") (pintype "passive"))
      (node (ref "X4") (pin "4") (pinfunction "4_4") (pintype "power_in"))
    )
    (net (code "37") (name "Net-(R19-Pad2)") (class "Default")
      (node (ref "R19") (pin "2") (pinfunction "2_2") (pintype "passive"))
      (node (ref "R20") (pin "2") (pinfunction "2_2") (pintype "passive"))
      (node (ref "X4") (pin "5") (pinfunction "5_5") (pintype "power_in"))
    )
    (net (code "38") (name "Net-(VD1-A)") (class "Default")
      (node (ref "R13") (pin "1") (pinfunction "1_1") (pintype "passive"))
      (node (ref "VD1") (pin "1") (pinfunction "A_1") (pintype "passive"))
    )
    (net (code "39") (name "Net-(VD2-A)") (class "Default")
      (node (ref "R17") (pin "1") (pinfunction "1_1") (pintype "passive"))
      (node (ref "VD2") (pin "1") (pinfunction "A_1") (pintype "passive"))
    )
    (net (code "40") (name "Net-(VT1-D)") (class "Default")
      (node (ref "VT1") (pin "3") (pinfunction "D_3") (pintype "passive"))
      (node (ref "X1") (pin "34") (pinfunction "34_34") (pintype "passive"))
      (node (ref "X1") (pin "35") (pinfunction "35_35") (pintype "passive"))
      (node (ref "X1") (pin "36") (pinfunction "36_36") (pintype "passive"))
    )
    (net (code "41") (name "Net-(VT1-G)") (class "Default")
      (node (ref "R5") (pin "2") (pinfunction "2_2") (pintype "passive"))
      (node (ref "R8") (pin "2") (pinfunction "2_2") (pintype "passive"))
      (node (ref "VT1") (pin "1") (pinfunction "G_1") (pintype "passive"))
    )
    (net (code "42") (name "Net-(VT2-G)") (class "Default")
      (node (ref "R21") (pin "2") (pinfunction "2_2") (pintype "passive"))
      (node (ref "R22") (pin "2") (pinfunction "2_2") (pintype "passive"))
      (node (ref "VT2") (pin "1") (pinfunction "G_1") (pintype "passive"))
    )
    (net (code "43") (name "unconnected-(D1-PA0{slash}WKUP-Pad10)") (class "Default")
      (node (ref "D1") (pin "10") (pinfunction "PA0/WKUP_10") (pintype "bidirectional"))
    )
    (net (code "44") (name "unconnected-(D1-PA1-Pad11)") (class "Default")
      (node (ref "D1") (pin "11") (pinfunction "PA1_11") (pintype "bidirectional"))
    )
    (net (code "45") (name "unconnected-(D1-PA8-Pad29)") (class "Default")
      (node (ref "D1") (pin "29") (pinfunction "PA8_29") (pintype "bidirectional"))
    )
    (net (code "46") (name "unconnected-(D1-PA9-Pad30)") (class "Default")
      (node (ref "D1") (pin "30") (pinfunction "PA9_30") (pintype "bidirectional"))
    )
    (net (code "47") (name "unconnected-(D1-PA10-Pad31)") (class "Default")
      (node (ref "D1") (pin "31") (pinfunction "PA10_31") (pintype "bidirectional"))
    )
    (net (code "48") (name "unconnected-(D1-PA11-Pad32)") (class "Default")
      (node (ref "D1") (pin "32") (pinfunction "PA11_32") (pintype "bidirectional"))
    )
    (net (code "49") (name "unconnected-(D1-PA12-Pad33)") (class "Default")
      (node (ref "D1") (pin "33") (pinfunction "PA12_33") (pintype "bidirectional"))
    )
    (net (code "50") (name "unconnected-(D1-PA15-Pad38)") (class "Default")
      (node (ref "D1") (pin "38") (pinfunction "PA15_38") (pintype "bidirectional"))
    )
    (net (code "51") (name "unconnected-(D1-PB2-Pad20)") (class "Default")
      (node (ref "D1") (pin "20") (pinfunction "PB2_20") (pintype "bidirectional"))
    )
    (net (code "52") (name "unconnected-(D1-PB8-Pad45)") (class "Default")
      (node (ref "D1") (pin "45") (pinfunction "PB8_45") (pintype "bidirectional"))
    )
    (net (code "53") (name "unconnected-(D1-PB9-Pad46)") (class "Default")
      (node (ref "D1") (pin "46") (pinfunction "PB9_46") (pintype "bidirectional"))
    )
    (net (code "54") (name "unconnected-(D1-PB10-Pad21)") (class "Default")
      (node (ref "D1") (pin "21") (pinfunction "PB10_21") (pintype "bidirectional"))
    )
    (net (code "55") (name "unconnected-(D1-PB12-Pad25)") (class "Default")
      (node (ref "D1") (pin "25") (pinfunction "PB12_25") (pintype "bidirectional"))
    )
    (net (code "56") (name "unconnected-(D1-PB13-Pad26)") (class "Default")
      (node (ref "D1") (pin "26") (pinfunction "PB13_26") (pintype "bidirectional"))
    )
    (net (code "57") (name "unconnected-(D1-PB14-Pad27)") (class "Default")
      (node (ref "D1") (pin "27") (pinfunction "PB14_27") (pintype "bidirectional"))
    )
    (net (code "58") (name "unconnected-(D1-PB15-Pad28)") (class "Default")
      (node (ref "D1") (pin "28") (pinfunction "PB15_28") (pintype "bidirectional"))
    )
    (net (code "59") (name "unconnected-(X1-Pad1)") (class "Default")
      (node (ref "X1") (pin "1") (pinfunction "1_1") (pintype "passive"))
    )
    (net (code "60") (name "unconnected-(X1-Pad2)") (class "Default")
      (node (ref "X1") (pin "2") (pinfunction "2_2") (pintype "passive"))
    )
    (net (code "61") (name "unconnected-(X1-Pad3)") (class "Default")
      (node (ref "X1") (pin "3") (pinfunction "3_3") (pintype "passive"))
    )
    (net (code "62") (name "unconnected-(X1-Pad4)") (class "Default")
      (node (ref "X1") (pin "4") (pinfunction "4_4") (pintype "passive"))
    )
    (net (code "63") (name "unconnected-(X1-Pad8)") (class "Default")
      (node (ref "X1") (pin "8") (pinfunction "8_8") (pintype "passive"))
    )
    (net (code "64") (name "unconnected-(X1-Pad12)") (class "Default")
      (node (ref "X1") (pin "12") (pinfunction "12_12") (pintype "passive"))
    )
    (net (code "65") (name "unconnected-(X1-Pad17)") (class "Default")
      (node (ref "X1") (pin "17") (pinfunction "17_17") (pintype "passive"))
    )
    (net (code "66") (name "unconnected-(X1-Pad18)") (class "Default")
      (node (ref "X1") (pin "18") (pinfunction "18_18") (pintype "passive"))
    )
    (net (code "67") (name "unconnected-(X1-Pad19)") (class "Default")
      (node (ref "X1") (pin "19") (pinfunction "19_19") (pintype "passive"))
    )
    (net (code "68") (name "unconnected-(X1-Pad20)") (class "Default")
      (node (ref "X1") (pin "20") (pinfunction "20_20") (pintype "passive"))
    )
    (net (code "69") (name "unconnected-(X1-Pad21)") (class "Default")
      (node (ref "X1") (pin "21") (pinfunction "21_21") (pintype "passive"))
    )
    (net (code "70") (name "unconnected-(X1-Pad22)") (class "Default")
      (node (ref "X1") (pin "22") (pinfunction "22_22") (pintype "passive"))
    )
    (net (code "71") (name "unconnected-(X1-Pad23)") (class "Default")
      (node (ref "X1") (pin "23") (pinfunction "23_23") (pintype "passive"))
    )
    (net (code "72") (name "unconnected-(X1-Pad24)") (class "Default")
      (node (ref "X1") (pin "24") (pinfunction "24_24") (pintype "passive"))
    )
    (net (code "73") (name "unconnected-(X1-Pad25)") (class "Default")
      (node (ref "X1") (pin "25") (pinfunction "25_25") (pintype "passive"))
    )
    (net (code "74") (name "unconnected-(X1-Pad26)") (class "Default")
      (node (ref "X1") (pin "26") (pinfunction "26_26") (pintype "passive"))
    )
    (net (code "75") (name "unconnected-(X1-Pad27)") (class "Default")
      (node (ref "X1") (pin "27") (pinfunction "27_27") (pintype "passive"))
    )
    (net (code "76") (name "unconnected-(X1-Pad28)") (class "Default")
      (node (ref "X1") (pin "28") (pinfunction "28_28") (pintype "passive"))
    )
    (net (code "77") (name "unconnected-(X1-Pad29)") (class "Default")
      (node (ref "X1") (pin "29") (pinfunction "29_29") (pintype "passive"))
    )
    (net (code "78") (name "unconnected-(X1-Pad30)") (class "Default")
      (node (ref "X1") (pin "30") (pinfunction "30_30") (pintype "passive"))
    )
    (net (code "79") (name "unconnected-(X1-Pad31)") (class "Default")
      (node (ref "X1") (pin "31") (pinfunction "31_31") (pintype "passive"))
    )
    (net (code "80") (name "unconnected-(X1-Pad32)") (class "Default")
      (node (ref "X1") (pin "32") (pinfunction "32_32") (pintype "passive"))
    )
  )
)
